# PushButtonQuadrant.net
KiCad netlist of a schematic drawn in Altium Designer
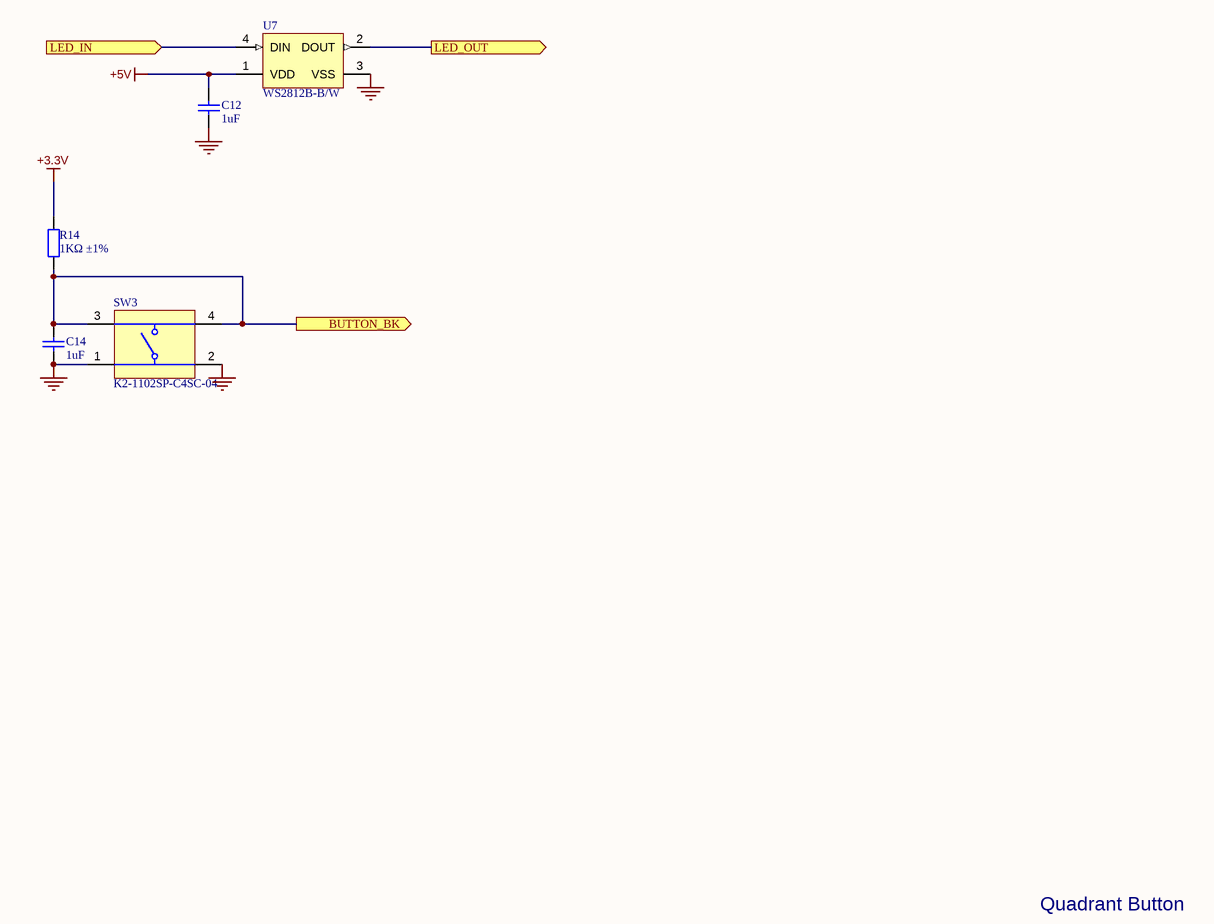
[diagram p0: PushButtonQuadrant.SchDoc]

(export (version "E")
  (design (tool "Eeschema 10.0.6"))
  (components
    (comp (ref "C12")
      (value "1uF")
      (footprint "0603_C")
      (description "Chip capacitors")
      (fields
        (field (name "MANUFACTURER") "Samsung Electro-Mechanics")
        (field (name "PARTNUMBER") "CL10A105KB8NNNC")
      )
      (libsource (lib "Cap") (part "0603 1uF (105) 10% 50V"))
    )
    (comp (ref "C14")
      (value "100nF")
      (footprint "0603_C")
      (description "Chip capacitors")
      (fields (field (name "MANUFACTURER") "YAGEO") (field (name "PARTNUMBER") "CC0603KRX7R9BB104"))
      (libsource (lib "Cap") (part "0603 100nF (104) 10% 50V"))
    )
    (comp (ref "R14")
      (value "1KΩ ±1%")
      (footprint "0603_R")
      (description "Chip resistor")
      (fields (field (name "MANUFACTURER") "Uniroyal Elec") (field (name "PARTNUMBER") "0603WAF1001T5E"))
      (libsource (lib "RES") (part "0603 1K (1001) 1%"))
    )
    (comp (ref "SW3")
      (value "K2-1102SP-C4SC-04")
      (footprint "TECO-FSM4JSMATR_V")
      (description "Top Actuated 50mA @ 12VDC Round Button SPST 6*6mm Tactile Switches ROHS")
      (libsource (lib "Altium Content Vault") (part "SW-SPST-4_A"))
    )
    (comp (ref "U7")
      (value "WS2812B-B/W")
      (footprint "ADA-RGB-1655_V")
      (fields (field (name "MANUFACTURER") "Worldsemi"))
      (libsource (lib "Altium Content Vault") (part "ADA-RGB-1655-4"))
    )
  )
  (nets
    (net (code "1") (name "+3.3V") (class "Default")
      (node (ref "R14") (pin "1") (pinfunction "1_1") (pintype "passive"))
    )
    (net (code "2") (name "+5V") (class "Default")
      (node (ref "C12") (pin "2") (pinfunction "2_2") (pintype "passive"))
      (node (ref "U7") (pin "1") (pinfunction "VDD_1") (pintype "power_in"))
    )
    (net (code "3") (name "/BUTTON_BK") (class "Default")
      (node (ref "C14") (pin "1") (pinfunction "1_1") (pintype "passive"))
      (node (ref "R14") (pin "2") (pinfunction "2_2") (pintype "passive"))
      (node (ref "SW3") (pin "3") (pinfunction "3_3") (pintype "passive"))
      (node (ref "SW3") (pin "4") (pinfunction "4_4") (pintype "passive"))
    )
    (net (code "4") (name "/LED_IN") (class "Default")
      (node (ref "U7") (pin "4") (pinfunction "DIN_4") (pintype "input"))
    )
    (net (code "5") (name "/LED_OUT") (class "Default")
      (node (ref "U7") (pin "2") (pinfunction "DOUT_2") (pintype "output"))
    )
    (net (code "6") (name "GND") (class "Default")
      (node (ref "C12") (pin "1") (pinfunction "1_1") (pintype "passive"))
      (node (ref "C14") (pin "2") (pinfunction "2_2") (pintype "passive"))
      (node (ref "SW3") (pin "1") (pinfunction "1_1") (pintype "passive"))
      (node (ref "SW3") (pin "2") (pinfunction "2_2") (pintype "passive"))
      (node (ref "U7") (pin "3") (pinfunction "VSS_3") (pintype "power_in"))
    )
  )
)
